# RFM50_Breakout_0.net
KiCad netlist of a schematic drawn in EAGLE
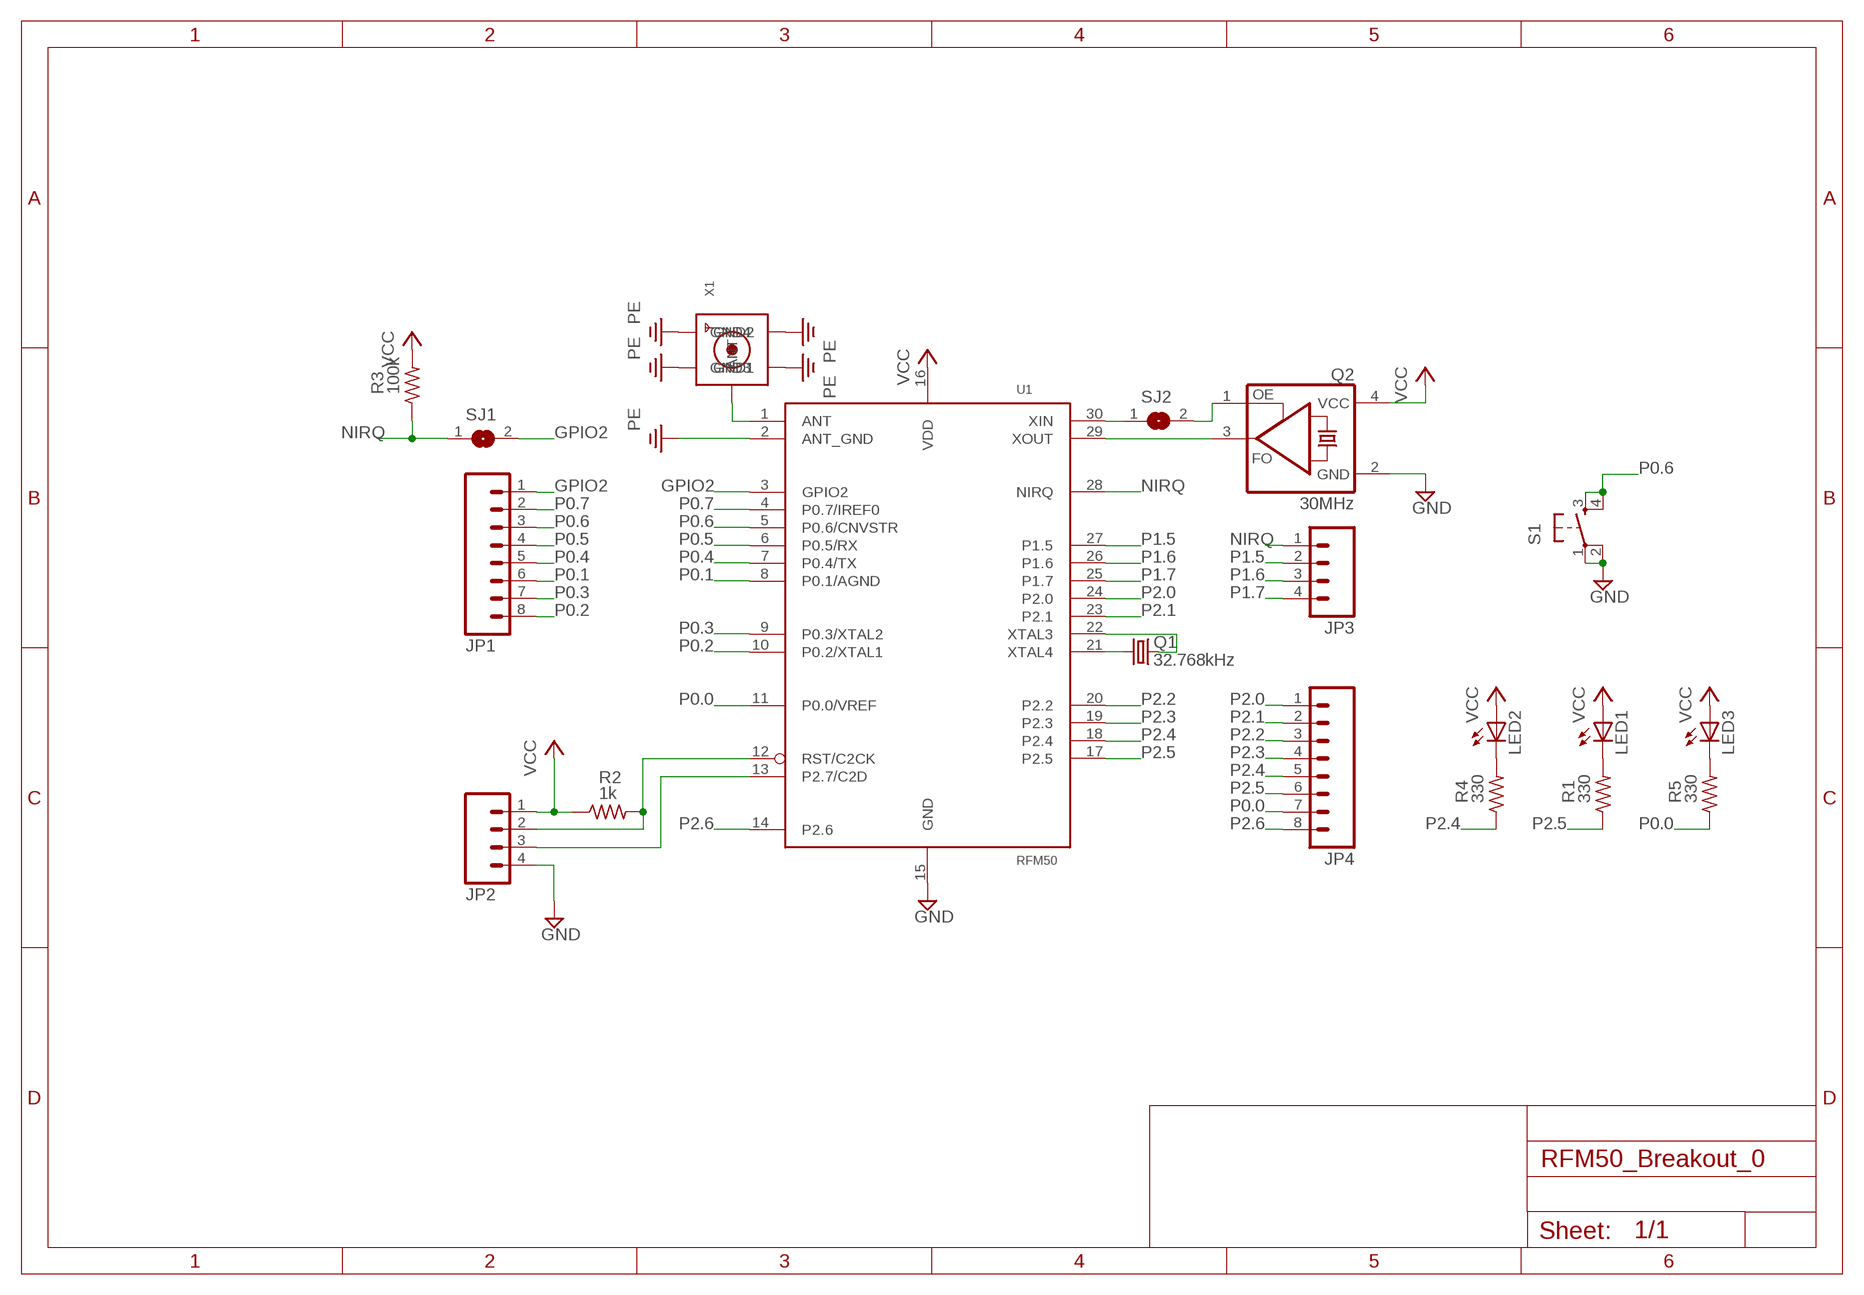
[diagram p0: schematic, sheet 1]

(export (version "E")
  (design (tool "Eeschema 10.0.6"))
  (components
    (comp (ref "JP1")
      (value "M081X08")
      (footprint "eagle-import:1X08")
      (libsource (lib "eagle-import") (part "M081X08"))
    )
    (comp (ref "JP2")
      (value "M04PTH")
      (footprint "eagle-import:1X04")
      (libsource (lib "eagle-import") (part "M04PTH"))
    )
    (comp (ref "JP3")
      (value "M04PTH")
      (footprint "eagle-import:1X04")
      (libsource (lib "eagle-import") (part "M04PTH"))
    )
    (comp (ref "JP4")
      (value "M081X08")
      (footprint "eagle-import:1X08")
      (libsource (lib "eagle-import") (part "M081X08"))
    )
    (comp (ref "LED1")
      (value "LED3MM")
      (footprint "eagle-import:LED3MM")
      (libsource (lib "eagle-import") (part "LED3MM"))
    )
    (comp (ref "LED2")
      (value "LED3MM")
      (footprint "eagle-import:LED3MM")
      (libsource (lib "eagle-import") (part "LED3MM"))
    )
    (comp (ref "LED3")
      (value "LED3MM")
      (footprint "eagle-import:LED3MM")
      (libsource (lib "eagle-import") (part "LED3MM"))
    )
    (comp (ref "Q1")
      (value "32.768kHz")
      (footprint "eagle-import:TC26H")
      (libsource (lib "eagle-import") (part "CRYSTALTC26H"))
    )
    (comp (ref "Q2")
      (value "30MHz")
      (footprint "eagle-import:ASF")
      (fields (field (name "MPN") "ASFLM1-50.000MHZ-C-T"))
      (libsource (lib "eagle-import") (part "ASFL"))
    )
    (comp (ref "R1")
      (value "330")
      (footprint "eagle-import:RCL_0204V")
      (libsource (lib "eagle-import") (part "RCL_R-US_0204/2V"))
    )
    (comp (ref "R2")
      (value "1k")
      (footprint "eagle-import:RCL_0204V")
      (libsource (lib "eagle-import") (part "RCL_R-US_0204/2V"))
    )
    (comp (ref "R3")
      (value "100k")
      (footprint "eagle-import:RCL_R0805")
      (libsource (lib "eagle-import") (part "RCL_R-US_R0805"))
    )
    (comp (ref "R4")
      (value "330")
      (footprint "eagle-import:RCL_0204V")
      (libsource (lib "eagle-import") (part "RCL_R-US_0204/2V"))
    )
    (comp (ref "R5")
      (value "330")
      (footprint "eagle-import:RCL_0204V")
      (libsource (lib "eagle-import") (part "RCL_R-US_0204/2V"))
    )
    (comp (ref "S1")
      (value "SWITCH-TACT_DTS-6")
      (footprint "eagle-import:SWITCH-TACT_DTS-6")
      (libsource (lib "eagle-import") (part "SWITCH-TACT_DTS-6"))
    )
    (comp (ref "SJ1") (value "SJ") (footprint "eagle-import:SJ") (libsource (lib "eagle-import") (part "SJ")))
    (comp (ref "SJ2") (value "SJ") (footprint "eagle-import:SJ") (libsource (lib "eagle-import") (part "SJ")))
    (comp (ref "U1")
      (value "RFM50")
      (footprint "eagle-import:RFM50")
      (libsource (lib "eagle-import") (part "RFM50"))
    )
    (comp (ref "X1")
      (value "SMACONNECTOR")
      (footprint "eagle-import:SMA90_DIP")
      (libsource (lib "eagle-import") (part "SMACONNECTOR"))
    )
  )
  (nets
    (net (code "1") (name "/GPIO2") (class "Default")
      (node (ref "JP1") (pin "1") (pinfunction "1_1") (pintype "passive"))
      (node (ref "SJ1") (pin "2") (pinfunction "2_2") (pintype "passive"))
      (node (ref "U1") (pin "3") (pinfunction "GPIO2_3") (pintype "bidirectional"))
    )
    (net (code "2") (name "/NIRQ") (class "Default")
      (node (ref "JP3") (pin "1") (pinfunction "1_1") (pintype "passive"))
      (node (ref "R3") (pin "1") (pinfunction "1_1") (pintype "passive"))
      (node (ref "SJ1") (pin "1") (pinfunction "1_1") (pintype "passive"))
      (node (ref "U1") (pin "28") (pinfunction "NIRQ_28") (pintype "output"))
    )
    (net (code "3") (name "/P0.0") (class "Default")
      (node (ref "JP4") (pin "7") (pinfunction "7_7") (pintype "passive"))
      (node (ref "R5") (pin "1") (pinfunction "1_1") (pintype "passive"))
      (node (ref "U1") (pin "11") (pinfunction "P0.0/VREF_11") (pintype "bidirectional"))
    )
    (net (code "4") (name "/P0.1") (class "Default")
      (node (ref "JP1") (pin "6") (pinfunction "6_6") (pintype "passive"))
      (node (ref "U1") (pin "8") (pinfunction "P0.1/AGND_8") (pintype "bidirectional"))
    )
    (net (code "5") (name "/P0.2") (class "Default")
      (node (ref "JP1") (pin "8") (pinfunction "8_8") (pintype "passive"))
      (node (ref "U1") (pin "10") (pinfunction "P0.2/XTAL1_10") (pintype "bidirectional"))
    )
    (net (code "6") (name "/P0.3") (class "Default")
      (node (ref "JP1") (pin "7") (pinfunction "7_7") (pintype "passive"))
      (node (ref "U1") (pin "9") (pinfunction "P0.3/XTAL2_9") (pintype "bidirectional"))
    )
    (net (code "7") (name "/P0.4") (class "Default")
      (node (ref "JP1") (pin "5") (pinfunction "5_5") (pintype "passive"))
      (node (ref "U1") (pin "7") (pinfunction "P0.4/TX_7") (pintype "bidirectional"))
    )
    (net (code "8") (name "/P0.5") (class "Default")
      (node (ref "JP1") (pin "4") (pinfunction "4_4") (pintype "passive"))
      (node (ref "U1") (pin "6") (pinfunction "P0.5/RX_6") (pintype "bidirectional"))
    )
    (net (code "9") (name "/P0.6") (class "Default")
      (node (ref "JP1") (pin "3") (pinfunction "3_3") (pintype "passive"))
      (node (ref "S1") (pin "3") (pinfunction "3_3") (pintype "passive"))
      (node (ref "S1") (pin "4") (pinfunction "4_4") (pintype "passive"))
      (node (ref "U1") (pin "5") (pinfunction "P0.6/CNVSTR_5") (pintype "bidirectional"))
    )
    (net (code "10") (name "/P0.7") (class "Default")
      (node (ref "JP1") (pin "2") (pinfunction "2_2") (pintype "passive"))
      (node (ref "U1") (pin "4") (pinfunction "P0.7/IREF0_4") (pintype "bidirectional"))
    )
    (net (code "11") (name "/P1.5") (class "Default")
      (node (ref "JP3") (pin "2") (pinfunction "2_2") (pintype "passive"))
      (node (ref "U1") (pin "27") (pinfunction "P1.5_27") (pintype "bidirectional"))
    )
    (net (code "12") (name "/P1.6") (class "Default")
      (node (ref "JP3") (pin "3") (pinfunction "3_3") (pintype "passive"))
      (node (ref "U1") (pin "26") (pinfunction "P1.6_26") (pintype "bidirectional"))
    )
    (net (code "13") (name "/P1.7") (class "Default")
      (node (ref "JP3") (pin "4") (pinfunction "4_4") (pintype "passive"))
      (node (ref "U1") (pin "25") (pinfunction "P1.7_25") (pintype "bidirectional"))
    )
    (net (code "14") (name "/P2.0") (class "Default")
      (node (ref "JP4") (pin "1") (pinfunction "1_1") (pintype "passive"))
      (node (ref "U1") (pin "24") (pinfunction "P2.0_24") (pintype "bidirectional"))
    )
    (net (code "15") (name "/P2.1") (class "Default")
      (node (ref "JP4") (pin "2") (pinfunction "2_2") (pintype "passive"))
      (node (ref "U1") (pin "23") (pinfunction "P2.1_23") (pintype "bidirectional"))
    )
    (net (code "16") (name "/P2.2") (class "Default")
      (node (ref "JP4") (pin "3") (pinfunction "3_3") (pintype "passive"))
      (node (ref "U1") (pin "20") (pinfunction "P2.2_20") (pintype "bidirectional"))
    )
    (net (code "17") (name "/P2.3") (class "Default")
      (node (ref "JP4") (pin "4") (pinfunction "4_4") (pintype "passive"))
      (node (ref "U1") (pin "19") (pinfunction "P2.3_19") (pintype "bidirectional"))
    )
    (net (code "18") (name "/P2.4") (class "Default")
      (node (ref "JP4") (pin "5") (pinfunction "5_5") (pintype "passive"))
      (node (ref "R4") (pin "1") (pinfunction "1_1") (pintype "passive"))
      (node (ref "U1") (pin "18") (pinfunction "P2.4_18") (pintype "bidirectional"))
    )
    (net (code "19") (name "/P2.5") (class "Default")
      (node (ref "JP4") (pin "6") (pinfunction "6_6") (pintype "passive"))
      (node (ref "R1") (pin "1") (pinfunction "1_1") (pintype "passive"))
      (node (ref "U1") (pin "17") (pinfunction "P2.5_17") (pintype "bidirectional"))
    )
    (net (code "20") (name "/P2.6") (class "Default")
      (node (ref "JP4") (pin "8") (pinfunction "8_8") (pintype "passive"))
      (node (ref "U1") (pin "14") (pinfunction "P2.6_14") (pintype "bidirectional"))
    )
    (net (code "21") (name "GND") (class "Default")
      (node (ref "JP2") (pin "4") (pinfunction "4_4") (pintype "passive"))
      (node (ref "Q2") (pin "2") (pinfunction "GND_2") (pintype "power_in"))
      (node (ref "S1") (pin "1") (pinfunction "1_1") (pintype "passive"))
      (node (ref "S1") (pin "2") (pinfunction "2_2") (pintype "passive"))
      (node (ref "U1") (pin "15") (pinfunction "GND_15") (pintype "bidirectional"))
    )
    (net (code "22") (name "Net-(LED1-C)") (class "Default")
      (node (ref "LED1") (pin "K") (pinfunction "C_K") (pintype "passive"))
      (node (ref "R1") (pin "2") (pinfunction "2_2") (pintype "passive"))
    )
    (net (code "23") (name "Net-(LED2-C)") (class "Default")
      (node (ref "LED2") (pin "K") (pinfunction "C_K") (pintype "passive"))
      (node (ref "R4") (pin "2") (pinfunction "2_2") (pintype "passive"))
    )
    (net (code "24") (name "Net-(LED3-C)") (class "Default")
      (node (ref "LED3") (pin "K") (pinfunction "C_K") (pintype "passive"))
      (node (ref "R5") (pin "2") (pinfunction "2_2") (pintype "passive"))
    )
    (net (code "25") (name "Net-(Q2-FO)") (class "Default")
      (node (ref "Q2") (pin "3") (pinfunction "FO_3") (pintype "output"))
      (node (ref "U1") (pin "29") (pinfunction "XOUT_29") (pintype "output"))
    )
    (net (code "26") (name "Net-(Q2-OE)") (class "Default")
      (node (ref "Q2") (pin "1") (pinfunction "OE_1") (pintype "input"))
      (node (ref "SJ2") (pin "2") (pinfunction "2_2") (pintype "passive"))
    )
    (net (code "27") (name "Net-(U1-ANT)") (class "Default")
      (node (ref "U1") (pin "1") (pinfunction "ANT_1") (pintype "bidirectional"))
      (node (ref "X1") (pin "ANTENNA") (pinfunction "ANT_ANTENNA") (pintype "bidirectional"))
    )
    (net (code "28") (name "Net-(U1-P2.7{slash}C2D)") (class "Default")
      (node (ref "JP2") (pin "3") (pinfunction "3_3") (pintype "passive"))
      (node (ref "U1") (pin "13") (pinfunction "P2.7/C2D_13") (pintype "bidirectional"))
    )
    (net (code "29") (name "Net-(U1-RST{slash}C2CK)") (class "Default")
      (node (ref "JP2") (pin "2") (pinfunction "2_2") (pintype "passive"))
      (node (ref "R2") (pin "2") (pinfunction "2_2") (pintype "passive"))
      (node (ref "U1") (pin "12") (pinfunction "RST/C2CK_12") (pintype "bidirectional"))
    )
    (net (code "30") (name "Net-(U1-XIN)") (class "Default")
      (node (ref "SJ2") (pin "1") (pinfunction "1_1") (pintype "passive"))
      (node (ref "U1") (pin "30") (pinfunction "XIN_30") (pintype "input"))
    )
    (net (code "31") (name "Net-(U1-XTAL3)") (class "Default")
      (node (ref "Q1") (pin "1") (pinfunction "1_1") (pintype "passive"))
      (node (ref "U1") (pin "22") (pinfunction "XTAL3_22") (pintype "bidirectional"))
    )
    (net (code "32") (name "Net-(U1-XTAL4)") (class "Default")
      (node (ref "Q1") (pin "2") (pinfunction "2_2") (pintype "passive"))
      (node (ref "U1") (pin "21") (pinfunction "XTAL4_21") (pintype "bidirectional"))
    )
    (net (code "33") (name "PE") (class "Default")
      (node (ref "U1") (pin "2") (pinfunction "ANT_GND_2") (pintype "bidirectional"))
      (node (ref "X1") (pin "GND1") (pinfunction "GND1_GND1") (pintype "power_in"))
      (node (ref "X1") (pin "GND2") (pinfunction "GND2_GND2") (pintype "power_in"))
      (node (ref "X1") (pin "GND3") (pinfunction "GND3_GND3") (pintype "power_in"))
      (node (ref "X1") (pin "GND4") (pinfunction "GND4_GND4") (pintype "power_in"))
    )
    (net (code "34") (name "VCC") (class "Default")
      (node (ref "JP2") (pin "1") (pinfunction "1_1") (pintype "passive"))
      (node (ref "LED1") (pin "A") (pinfunction "A_A") (pintype "passive"))
      (node (ref "LED2") (pin "A") (pinfunction "A_A") (pintype "passive"))
      (node (ref "LED3") (pin "A") (pinfunction "A_A") (pintype "passive"))
      (node (ref "Q2") (pin "4") (pinfunction "VCC_4") (pintype "power_in"))
      (node (ref "R2") (pin "1") (pinfunction "1_1") (pintype "passive"))
      (node (ref "R3") (pin "2") (pinfunction "2_2") (pintype "passive"))
      (node (ref "U1") (pin "16") (pinfunction "VDD_16") (pintype "power_in"))
    )
  )
)
